# Ultrasonic_mbed_casa.net
KiCad netlist of a schematic drawn in Altium Designer
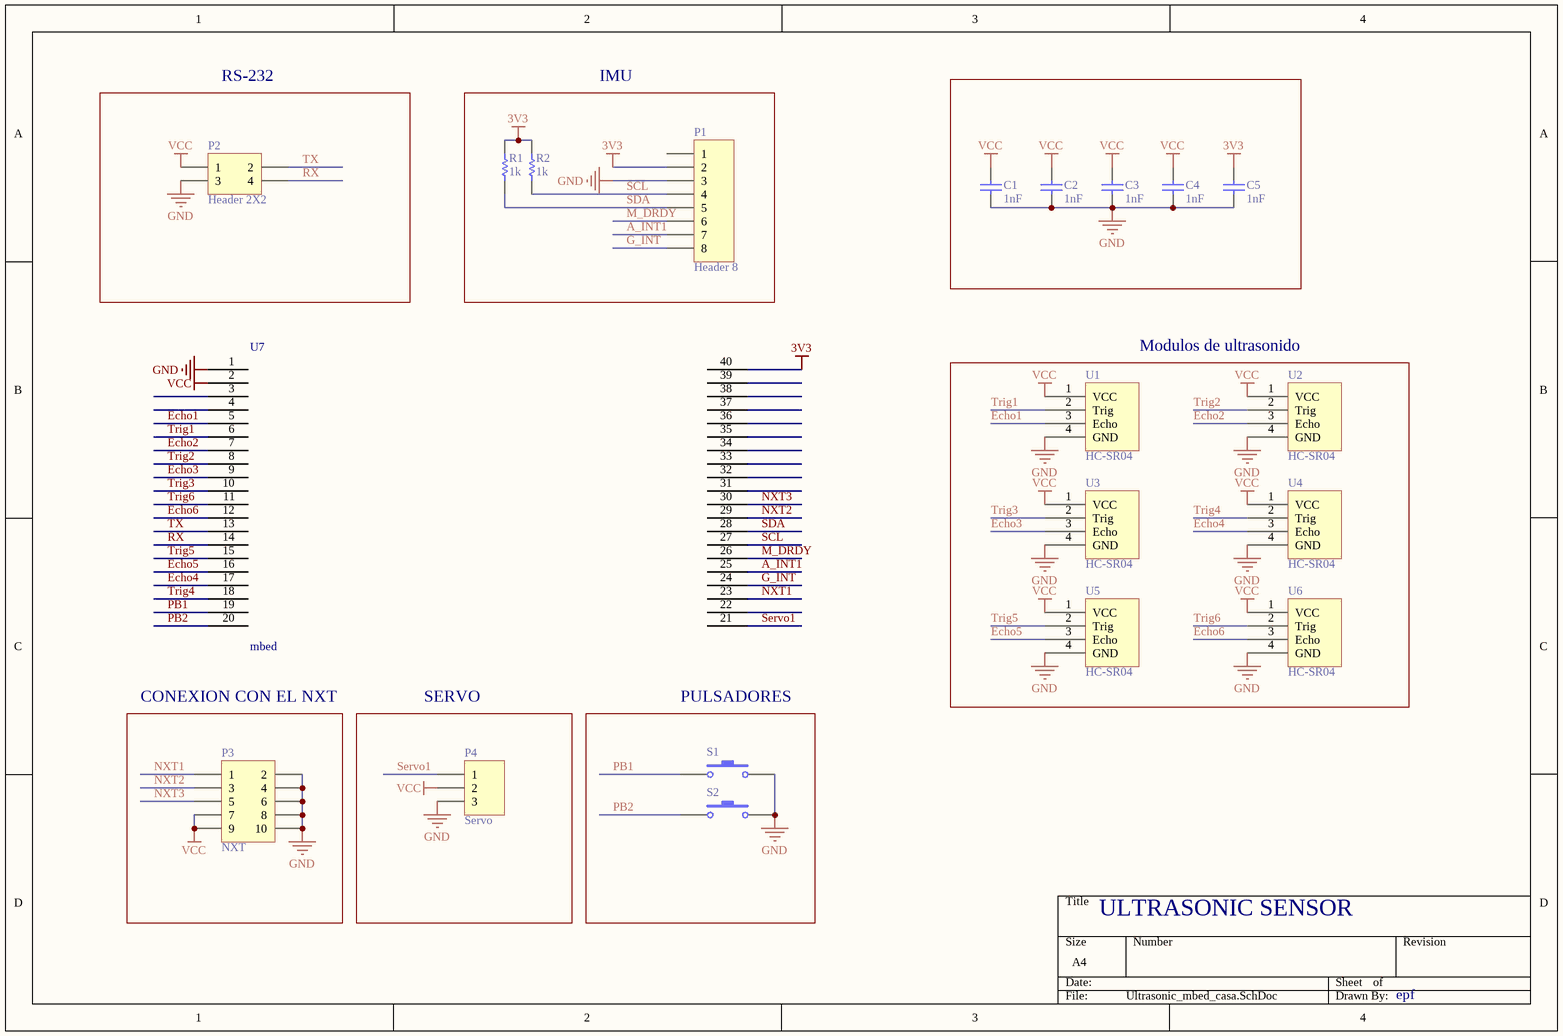
[diagram p0: Ultrasonic_mbed_casa.SchDoc]

(export (version "E")
  (design (tool "Eeschema 10.0.6"))
  (components
    (comp (ref "C1")
      (value "1nF")
      (footprint "CAP0805")
      (fields (field (name "Comment") "Capacitor"))
      (libsource (lib "epf") (part "Cap"))
    )
    (comp (ref "C2")
      (value "1nF")
      (footprint "CAP0805")
      (fields (field (name "Comment") "Capacitor"))
      (libsource (lib "epf") (part "Cap"))
    )
    (comp (ref "C3")
      (value "1nF")
      (footprint "CAP0805")
      (fields (field (name "Comment") "Capacitor"))
      (libsource (lib "epf") (part "Cap"))
    )
    (comp (ref "C4")
      (value "1nF")
      (footprint "CAP0805")
      (fields (field (name "Comment") "Capacitor"))
      (libsource (lib "epf") (part "Cap"))
    )
    (comp (ref "C5")
      (value "1nF")
      (footprint "CAP0805")
      (fields (field (name "Comment") "Capacitor"))
      (libsource (lib "epf") (part "Cap"))
    )
    (comp (ref "P1")
      (value "Header 8")
      (footprint "HDR1X8")
      (description "Header, 8-Pin")
      (fields (field (name "PUBLISHER") "Altium Limited"))
      (libsource (lib "Miscellaneous Connectors") (part "Header 8"))
    )
    (comp (ref "P2")
      (value "Header 2X2")
      (footprint "HDR2X2")
      (description "Header, 2-Pin, Dual row")
      (fields (field (name "PUBLISHER") "Altium Limited"))
      (libsource (lib "Miscellaneous Connectors") (part "Header 2X2"))
    )
    (comp (ref "P3")
      (value "NXT")
      (footprint "HDR2X5")
      (description "Header, 5-Pin, Dual row")
      (fields (field (name "PUBLISHER") "Altium Limited"))
      (libsource (lib "epf") (part "Header 5X2"))
    )
    (comp (ref "P4")
      (value "Servo")
      (footprint "HDR1X3")
      (description "Header, 3-Pin")
      (fields (field (name "PUBLISHER") "Altium Limited"))
      (libsource (lib "Miscellaneous Connectors") (part "Header 3"))
    )
    (comp (ref "R1")
      (value "1k")
      (footprint "RES0805")
      (fields (field (name "Comment") "Resistor"))
      (libsource (lib "epf") (part "Res"))
    )
    (comp (ref "R2")
      (value "1k")
      (footprint "RES0805")
      (fields (field (name "Comment") "Resistor"))
      (libsource (lib "epf") (part "Res"))
    )
    (comp (ref "S1")
      (value "SW-PB")
      (footprint "SW-PB6mm - 2")
      (description "Switch")
      (fields (field (name "PUBLISHER") "Altium Limited"))
      (libsource (lib "epf") (part "SW-PB"))
    )
    (comp (ref "S2")
      (value "SW-PB")
      (footprint "SW-PB6mm - 2")
      (description "Switch")
      (fields (field (name "PUBLISHER") "Altium Limited"))
      (libsource (lib "epf") (part "SW-PB"))
    )
    (comp (ref "U1")
      (value "HC-SR04")
      (footprint "HC-SR04")
      (description "Ultrasonic module")
      (libsource (lib "epf") (part "HC-SR04"))
    )
    (comp (ref "U2")
      (value "HC-SR04")
      (footprint "HC-SR04")
      (description "Ultrasonic module")
      (libsource (lib "epf") (part "HC-SR04"))
    )
    (comp (ref "U3")
      (value "HC-SR04")
      (footprint "HC-SR04")
      (description "Ultrasonic module")
      (libsource (lib "epf") (part "HC-SR04"))
    )
    (comp (ref "U4")
      (value "HC-SR04")
      (footprint "HC-SR04")
      (description "Ultrasonic module")
      (libsource (lib "epf") (part "HC-SR04"))
    )
    (comp (ref "U5")
      (value "HC-SR04")
      (footprint "HC-SR04")
      (description "Ultrasonic module")
      (libsource (lib "epf") (part "HC-SR04"))
    )
    (comp (ref "U6")
      (value "HC-SR04")
      (footprint "HC-SR04")
      (description "Ultrasonic module")
      (libsource (lib "epf") (part "HC-SR04"))
    )
    (comp (ref "U7") (value "mbed") (footprint "mbed") (libsource (lib "epf") (part "mbed")))
  )
  (nets
    (net (code "1") (name "/A_INT1") (class "Default")
      (node (ref "P1") (pin "7") (pinfunction "7_7") (pintype "passive"))
      (node (ref "U7") (pin "25") (pinfunction "25_25") (pintype "passive"))
    )
    (net (code "2") (name "/Echo1") (class "Default")
      (node (ref "U1") (pin "3") (pinfunction "Echo_3") (pintype "passive"))
      (node (ref "U7") (pin "5") (pinfunction "5_5") (pintype "passive"))
    )
    (net (code "3") (name "/Echo2") (class "Default")
      (node (ref "U2") (pin "3") (pinfunction "Echo_3") (pintype "passive"))
      (node (ref "U7") (pin "7") (pinfunction "7_7") (pintype "passive"))
    )
    (net (code "4") (name "/Echo3") (class "Default")
      (node (ref "U3") (pin "3") (pinfunction "Echo_3") (pintype "passive"))
      (node (ref "U7") (pin "9") (pinfunction "9_9") (pintype "passive"))
    )
    (net (code "5") (name "/Echo4") (class "Default")
      (node (ref "U4") (pin "3") (pinfunction "Echo_3") (pintype "passive"))
      (node (ref "U7") (pin "17") (pinfunction "17_17") (pintype "passive"))
    )
    (net (code "6") (name "/Echo5") (class "Default")
      (node (ref "U5") (pin "3") (pinfunction "Echo_3") (pintype "passive"))
      (node (ref "U7") (pin "16") (pinfunction "16_16") (pintype "passive"))
    )
    (net (code "7") (name "/Echo6") (class "Default")
      (node (ref "U6") (pin "3") (pinfunction "Echo_3") (pintype "passive"))
      (node (ref "U7") (pin "12") (pinfunction "12_12") (pintype "passive"))
    )
    (net (code "8") (name "/G_INT") (class "Default")
      (node (ref "P1") (pin "8") (pinfunction "8_8") (pintype "passive"))
      (node (ref "U7") (pin "24") (pinfunction "24_24") (pintype "passive"))
    )
    (net (code "9") (name "/M_DRDY") (class "Default")
      (node (ref "P1") (pin "6") (pinfunction "6_6") (pintype "passive"))
      (node (ref "U7") (pin "26") (pinfunction "26_26") (pintype "passive"))
    )
    (net (code "10") (name "/NXT1") (class "Default")
      (node (ref "P3") (pin "1") (pinfunction "1_1") (pintype "passive"))
      (node (ref "U7") (pin "23") (pinfunction "23_23") (pintype "passive"))
    )
    (net (code "11") (name "/NXT2") (class "Default")
      (node (ref "P3") (pin "3") (pinfunction "3_3") (pintype "passive"))
      (node (ref "U7") (pin "29") (pinfunction "29_29") (pintype "passive"))
    )
    (net (code "12") (name "/NXT3") (class "Default")
      (node (ref "P3") (pin "5") (pinfunction "5_5") (pintype "passive"))
      (node (ref "U7") (pin "30") (pinfunction "30_30") (pintype "passive"))
    )
    (net (code "13") (name "/PB1") (class "Default")
      (node (ref "S1") (pin "1") (pinfunction "1_1") (pintype "passive"))
      (node (ref "U7") (pin "19") (pinfunction "19_19") (pintype "passive"))
    )
    (net (code "14") (name "/PB2") (class "Default")
      (node (ref "S2") (pin "1") (pinfunction "1_1") (pintype "passive"))
      (node (ref "U7") (pin "20") (pinfunction "20_20") (pintype "passive"))
    )
    (net (code "15") (name "/RX") (class "Default")
      (node (ref "P2") (pin "4") (pinfunction "4_4") (pintype "passive"))
      (node (ref "U7") (pin "14") (pinfunction "14_14") (pintype "passive"))
    )
    (net (code "16") (name "/SCL") (class "Default")
      (node (ref "P1") (pin "4") (pinfunction "4_4") (pintype "passive"))
      (node (ref "R2") (pin "2") (pinfunction "2_2") (pintype "passive"))
      (node (ref "U7") (pin "27") (pinfunction "27_27") (pintype "passive"))
    )
    (net (code "17") (name "/SDA") (class "Default")
      (node (ref "P1") (pin "5") (pinfunction "5_5") (pintype "passive"))
      (node (ref "R1") (pin "2") (pinfunction "2_2") (pintype "passive"))
      (node (ref "U7") (pin "28") (pinfunction "28_28") (pintype "passive"))
    )
    (net (code "18") (name "/Servo1") (class "Default")
      (node (ref "P4") (pin "1") (pinfunction "1_1") (pintype "passive"))
      (node (ref "U7") (pin "21") (pinfunction "21_21") (pintype "passive"))
    )
    (net (code "19") (name "/TX") (class "Default")
      (node (ref "P2") (pin "2") (pinfunction "2_2") (pintype "passive"))
      (node (ref "U7") (pin "13") (pinfunction "13_13") (pintype "passive"))
    )
    (net (code "20") (name "/Trig1") (class "Default")
      (node (ref "U1") (pin "2") (pinfunction "Trig_2") (pintype "passive"))
      (node (ref "U7") (pin "6") (pinfunction "6_6") (pintype "passive"))
    )
    (net (code "21") (name "/Trig2") (class "Default")
      (node (ref "U2") (pin "2") (pinfunction "Trig_2") (pintype "passive"))
      (node (ref "U7") (pin "8") (pinfunction "8_8") (pintype "passive"))
    )
    (net (code "22") (name "/Trig3") (class "Default")
      (node (ref "U3") (pin "2") (pinfunction "Trig_2") (pintype "passive"))
      (node (ref "U7") (pin "10") (pinfunction "10_10") (pintype "passive"))
    )
    (net (code "23") (name "/Trig4") (class "Default")
      (node (ref "U4") (pin "2") (pinfunction "Trig_2") (pintype "passive"))
      (node (ref "U7") (pin "18") (pinfunction "18_18") (pintype "passive"))
    )
    (net (code "24") (name "/Trig5") (class "Default")
      (node (ref "U5") (pin "2") (pinfunction "Trig_2") (pintype "passive"))
      (node (ref "U7") (pin "15") (pinfunction "15_15") (pintype "passive"))
    )
    (net (code "25") (name "/Trig6") (class "Default")
      (node (ref "U6") (pin "2") (pinfunction "Trig_2") (pintype "passive"))
      (node (ref "U7") (pin "11") (pinfunction "11_11") (pintype "passive"))
    )
    (net (code "26") (name "3V3") (class "Default")
      (node (ref "C5") (pin "2") (pinfunction "2_2") (pintype "passive"))
      (node (ref "P1") (pin "2") (pinfunction "2_2") (pintype "passive"))
      (node (ref "R1") (pin "1") (pinfunction "1_1") (pintype "passive"))
      (node (ref "R2") (pin "1") (pinfunction "1_1") (pintype "passive"))
      (node (ref "U7") (pin "40") (pinfunction "40_40") (pintype "passive"))
    )
    (net (code "27") (name "GND") (class "Default")
      (node (ref "C1") (pin "1") (pinfunction "1_1") (pintype "passive"))
      (node (ref "C2") (pin "1") (pinfunction "1_1") (pintype "passive"))
      (node (ref "C3") (pin "1") (pinfunction "1_1") (pintype "passive"))
      (node (ref "C4") (pin "1") (pinfunction "1_1") (pintype "passive"))
      (node (ref "C5") (pin "1") (pinfunction "1_1") (pintype "passive"))
      (node (ref "P1") (pin "3") (pinfunction "3_3") (pintype "passive"))
      (node (ref "P2") (pin "3") (pinfunction "3_3") (pintype "passive"))
      (node (ref "P3") (pin "10") (pinfunction "10_10") (pintype "passive"))
      (node (ref "P3") (pin "2") (pinfunction "2_2") (pintype "passive"))
      (node (ref "P3") (pin "4") (pinfunction "4_4") (pintype "passive"))
      (node (ref "P3") (pin "6") (pinfunction "6_6") (pintype "passive"))
      (node (ref "P3") (pin "8") (pinfunction "8_8") (pintype "passive"))
      (node (ref "P4") (pin "3") (pinfunction "3_3") (pintype "passive"))
      (node (ref "S1") (pin "2") (pinfunction "2_2") (pintype "passive"))
      (node (ref "S2") (pin "2") (pinfunction "2_2") (pintype "passive"))
      (node (ref "U1") (pin "4") (pinfunction "GND_4") (pintype "passive"))
      (node (ref "U2") (pin "4") (pinfunction "GND_4") (pintype "passive"))
      (node (ref "U3") (pin "4") (pinfunction "GND_4") (pintype "passive"))
      (node (ref "U4") (pin "4") (pinfunction "GND_4") (pintype "passive"))
      (node (ref "U5") (pin "4") (pinfunction "GND_4") (pintype "passive"))
      (node (ref "U6") (pin "4") (pinfunction "GND_4") (pintype "passive"))
      (node (ref "U7") (pin "1") (pinfunction "1_1") (pintype "passive"))
    )
    (net (code "28") (name "VCC") (class "Default")
      (node (ref "C1") (pin "2") (pinfunction "2_2") (pintype "passive"))
      (node (ref "C2") (pin "2") (pinfunction "2_2") (pintype "passive"))
      (node (ref "C3") (pin "2") (pinfunction "2_2") (pintype "passive"))
      (node (ref "C4") (pin "2") (pinfunction "2_2") (pintype "passive"))
      (node (ref "P2") (pin "1") (pinfunction "1_1") (pintype "passive"))
      (node (ref "P3") (pin "7") (pinfunction "7_7") (pintype "passive"))
      (node (ref "P3") (pin "9") (pinfunction "9_9") (pintype "passive"))
      (node (ref "P4") (pin "2") (pinfunction "2_2") (pintype "passive"))
      (node (ref "U1") (pin "1") (pinfunction "VCC_1") (pintype "passive"))
      (node (ref "U2") (pin "1") (pinfunction "VCC_1") (pintype "passive"))
      (node (ref "U3") (pin "1") (pinfunction "VCC_1") (pintype "passive"))
      (node (ref "U4") (pin "1") (pinfunction "VCC_1") (pintype "passive"))
      (node (ref "U5") (pin "1") (pinfunction "VCC_1") (pintype "passive"))
      (node (ref "U6") (pin "1") (pinfunction "VCC_1") (pintype "passive"))
      (node (ref "U7") (pin "2") (pinfunction "2_2") (pintype "passive"))
    )
    (net (code "29") (name "unconnected-(P1-Pad1)") (class "Default")
      (node (ref "P1") (pin "1") (pinfunction "1_1") (pintype "passive"))
    )
    (net (code "30") (name "unconnected-(U7-Pad3)") (class "Default")
      (node (ref "U7") (pin "3") (pinfunction "3_3") (pintype "passive"))
    )
    (net (code "31") (name "unconnected-(U7-Pad4)") (class "Default")
      (node (ref "U7") (pin "4") (pinfunction "4_4") (pintype "passive"))
    )
    (net (code "32") (name "unconnected-(U7-Pad22)") (class "Default")
      (node (ref "U7") (pin "22") (pinfunction "22_22") (pintype "passive"))
    )
    (net (code "33") (name "unconnected-(U7-Pad31)") (class "Default")
      (node (ref "U7") (pin "31") (pinfunction "31_31") (pintype "passive"))
    )
    (net (code "34") (name "unconnected-(U7-Pad32)") (class "Default")
      (node (ref "U7") (pin "32") (pinfunction "32_32") (pintype "passive"))
    )
    (net (code "35") (name "unconnected-(U7-Pad33)") (class "Default")
      (node (ref "U7") (pin "33") (pinfunction "33_33") (pintype "passive"))
    )
    (net (code "36") (name "unconnected-(U7-Pad34)") (class "Default")
      (node (ref "U7") (pin "34") (pinfunction "34_34") (pintype "passive"))
    )
    (net (code "37") (name "unconnected-(U7-Pad35)") (class "Default")
      (node (ref "U7") (pin "35") (pinfunction "35_35") (pintype "passive"))
    )
    (net (code "38") (name "unconnected-(U7-Pad36)") (class "Default")
      (node (ref "U7") (pin "36") (pinfunction "36_36") (pintype "passive"))
    )
    (net (code "39") (name "unconnected-(U7-Pad37)") (class "Default")
      (node (ref "U7") (pin "37") (pinfunction "37_37") (pintype "passive"))
    )
    (net (code "40") (name "unconnected-(U7-Pad38)") (class "Default")
      (node (ref "U7") (pin "38") (pinfunction "38_38") (pintype "passive"))
    )
    (net (code "41") (name "unconnected-(U7-Pad39)") (class "Default")
      (node (ref "U7") (pin "39") (pinfunction "39_39") (pintype "passive"))
    )
  )
)
